# CE842170047_SHEET4.net
KiCad netlist of a schematic drawn in Altium Designer
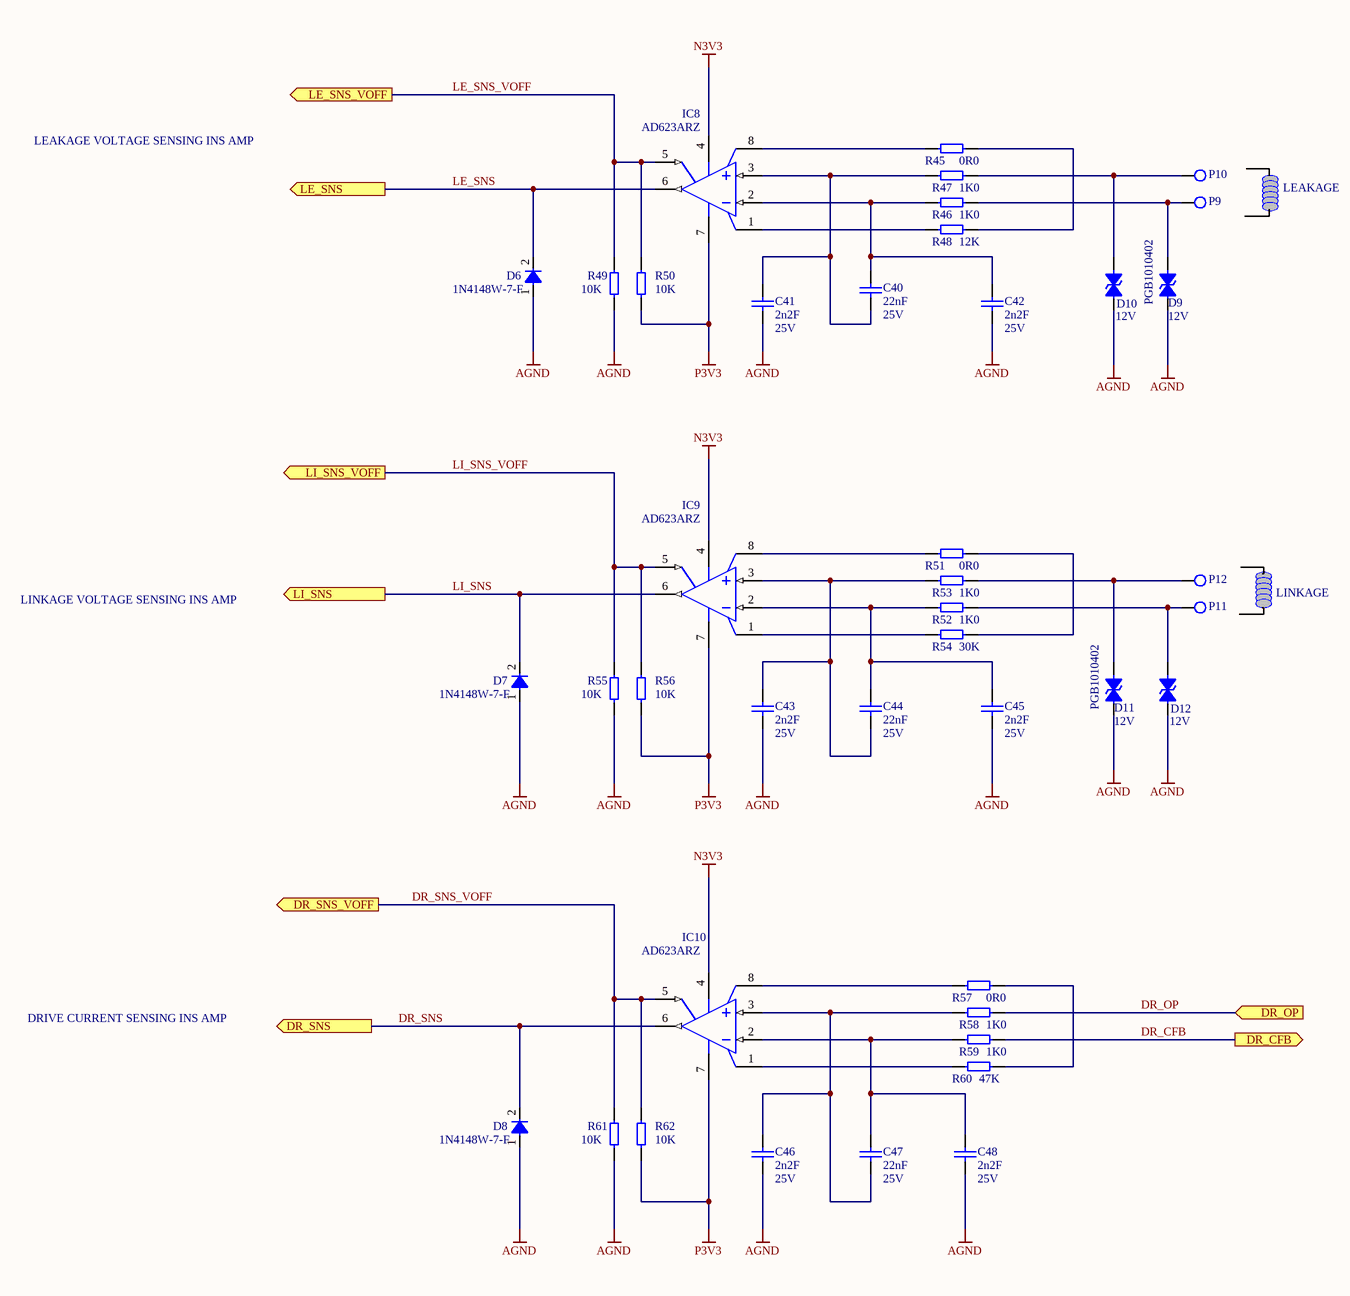
[diagram p0: CE842170047_SHEET4.SchDoc]

(export (version "E")
  (design (tool "Eeschema 10.0.6"))
  (components
    (comp (ref "C40")
      (value "22nF")
      (footprint "C0603")
      (description "CAPACITOR CERAMIC 0603 25V 10% X7R 22nF")
      (fields
        (field (name "VOLTAGE") "25V")
        (field (name "PII_PARTNUMBER") "KK/96159/3434")
        (field (name "TOLERANCE") "10%")
      )
      (libsource (lib "AltiumComponents") (part "CAP_GENERIC"))
    )
    (comp (ref "C41")
      (value "2n2F")
      (footprint "C0603")
      (description "CAPACITOR_2.2nF_10%_25V_603")
      (fields
        (field (name "VOLTAGE") "25V")
        (field (name "PII_PARTNUMBER") "KK/96159/4334")
        (field (name "TOLERANCE") "10%")
      )
      (libsource (lib "AltiumComponents") (part "CAP_GENERIC"))
    )
    (comp (ref "C42")
      (value "2n2F")
      (footprint "C0603")
      (description "CAPACITOR_2.2nF_10%_25V_603")
      (fields
        (field (name "VOLTAGE") "25V")
        (field (name "PII_PARTNUMBER") "KK/96159/4334")
        (field (name "TOLERANCE") "10%")
      )
      (libsource (lib "AltiumComponents") (part "CAP_GENERIC"))
    )
    (comp (ref "C43")
      (value "2n2F")
      (footprint "C0603")
      (description "CAPACITOR_2.2nF_10%_25V_603")
      (fields
        (field (name "VOLTAGE") "25V")
        (field (name "PII_PARTNUMBER") "KK/96159/4334")
        (field (name "TOLERANCE") "10%")
      )
      (libsource (lib "AltiumComponents") (part "CAP_GENERIC"))
    )
    (comp (ref "C44")
      (value "22nF")
      (footprint "C0603")
      (description "CAPACITOR CERAMIC 0603 25V 10% X7R 22nF")
      (fields
        (field (name "VOLTAGE") "25V")
        (field (name "PII_PARTNUMBER") "KK/96159/3434")
        (field (name "TOLERANCE") "10%")
      )
      (libsource (lib "AltiumComponents") (part "CAP_GENERIC"))
    )
    (comp (ref "C45")
      (value "2n2F")
      (footprint "C0603")
      (description "CAPACITOR_2.2nF_10%_25V_603")
      (fields
        (field (name "VOLTAGE") "25V")
        (field (name "PII_PARTNUMBER") "KK/96159/4334")
        (field (name "TOLERANCE") "10%")
      )
      (libsource (lib "AltiumComponents") (part "CAP_GENERIC"))
    )
    (comp (ref "C46")
      (value "2n2F")
      (footprint "C0603")
      (description "CAPACITOR_2.2nF_10%_25V_603")
      (fields
        (field (name "VOLTAGE") "25V")
        (field (name "PII_PARTNUMBER") "KK/96159/4334")
        (field (name "TOLERANCE") "10%")
      )
      (libsource (lib "AltiumComponents") (part "CAP_GENERIC"))
    )
    (comp (ref "C47")
      (value "22nF")
      (footprint "C0603")
      (description "CAPACITOR CERAMIC 0603 25V 10% X7R 22nF")
      (fields
        (field (name "VOLTAGE") "25V")
        (field (name "PII_PARTNUMBER") "KK/96159/3434")
        (field (name "TOLERANCE") "10%")
      )
      (libsource (lib "AltiumComponents") (part "CAP_GENERIC"))
    )
    (comp (ref "C48")
      (value "2n2F")
      (footprint "C0603")
      (description "CAPACITOR_2.2nF_10%_25V_603")
      (fields
        (field (name "VOLTAGE") "25V")
        (field (name "PII_PARTNUMBER") "KK/96159/4334")
        (field (name "TOLERANCE") "10%")
      )
      (libsource (lib "AltiumComponents") (part "CAP_GENERIC"))
    )
    (comp (ref "D6")
      (value "KK/95048/0189")
      (footprint "SOD-123")
      (description "DIODE SWITCHING POWER")
      (fields
        (field (name "MF_PARTNUMBER") "1N4148W-7-F")
        (field (name "POWER") "2A")
        (field (name "VOLTAGE") "100V")
      )
      (libsource (lib "AltiumComponents") (part "DIODE_GENERIC"))
    )
    (comp (ref "D7")
      (value "KK/95048/0189")
      (footprint "SOD-123")
      (description "DIODE SWITCHING POWER")
      (fields
        (field (name "MF_PARTNUMBER") "1N4148W-7-F")
        (field (name "POWER") "2A")
        (field (name "VOLTAGE") "100V")
      )
      (libsource (lib "AltiumComponents") (part "DIODE_GENERIC"))
    )
    (comp (ref "D8")
      (value "KK/95048/0189")
      (footprint "SOD-123")
      (description "DIODE SWITCHING POWER")
      (fields
        (field (name "MF_PARTNUMBER") "1N4148W-7-F")
        (field (name "POWER") "2A")
        (field (name "VOLTAGE") "100V")
      )
      (libsource (lib "AltiumComponents") (part "DIODE_GENERIC"))
    )
    (comp (ref "D9")
      (value "KK/95070/0036")
      (footprint "ESD0402")
      (description "SUPPRESSOR ESD,SMD,0402,12VDC,LIF,PGB1010402")
      (fields
        (field (name "MF_PARTNUMBER") "PGB1010402")
        (field (name "VOLTAGE") "12V")
        (field (name "MANUFACTURER") "LITTELFUSE")
      )
      (libsource (lib "AltiumComponents") (part "TVS_DIODE_BIDIR"))
    )
    (comp (ref "D10")
      (value "KK/95070/0036")
      (footprint "ESD0402")
      (description "SUPPRESSOR ESD,SMD,0402,12VDC,LIF,PGB1010402")
      (fields
        (field (name "MF_PARTNUMBER") "PGB1010402")
        (field (name "VOLTAGE") "12V")
        (field (name "MANUFACTURER") "LITTELFUSE")
      )
      (libsource (lib "AltiumComponents") (part "TVS_DIODE_BIDIR"))
    )
    (comp (ref "D11")
      (value "KK/95070/0036")
      (footprint "ESD0402")
      (description "SUPPRESSOR ESD,SMD,0402,12VDC,LIF,PGB1010402")
      (fields
        (field (name "MF_PARTNUMBER") "PGB1010402")
        (field (name "VOLTAGE") "12V")
        (field (name "MANUFACTURER") "LITTELFUSE")
      )
      (libsource (lib "AltiumComponents") (part "TVS_DIODE_BIDIR"))
    )
    (comp (ref "D12")
      (value "KK/95070/0036")
      (footprint "ESD0402")
      (description "SUPPRESSOR ESD,SMD,0402,12VDC,LIF,PGB1010402")
      (fields
        (field (name "MF_PARTNUMBER") "PGB1010402")
        (field (name "VOLTAGE") "12V")
        (field (name "MANUFACTURER") "LITTELFUSE")
      )
      (libsource (lib "AltiumComponents") (part "TVS_DIODE_BIDIR"))
    )
    (comp (ref "IC8")
      (value "KK/95312/0245")
      (footprint "SOIC-8")
      (description "SINGLE RAIL to RAIL INSTRUMENTATION AMPLIFIER")
      (fields
        (field (name "MANUFACTURER") "Analog Devices")
        (field (name "MANUFACTURER PART NUMBER") "AD623ARZ")
        (field (name "MF_PARTNUMBER") "AD623ARZ")
      )
      (libsource (lib "AltiumComponents") (part "AD623"))
    )
    (comp (ref "IC9")
      (value "KK/95312/0245")
      (footprint "SOIC-8")
      (description "SINGLE RAIL to RAIL INSTRUMENTATION AMPLIFIER")
      (fields
        (field (name "MANUFACTURER") "Analog Devices")
        (field (name "MANUFACTURER PART NUMBER") "AD623ARZ")
        (field (name "MF_PARTNUMBER") "AD623ARZ")
      )
      (libsource (lib "AltiumComponents") (part "AD623"))
    )
    (comp (ref "IC10")
      (value "KK/95312/0245")
      (footprint "SOIC-8")
      (description "SINGLE RAIL to RAIL INSTRUMENTATION AMPLIFIER")
      (fields
        (field (name "MANUFACTURER") "Analog Devices")
        (field (name "MANUFACTURER PART NUMBER") "AD623ARZ")
        (field (name "MF_PARTNUMBER") "AD623ARZ")
      )
      (libsource (lib "AltiumComponents") (part "AD623"))
    )
    (comp (ref "P9")
      (value "TESTPAD1")
      (footprint "P0.8xH0.5")
      (description "P0.8 X H0.5 X 0.9SM")
      (fields (field (name "MANUFACTURER") "PCB MANUFACTURER"))
      (libsource (lib "AltiumComponents") (part "TP_GENERIC"))
    )
    (comp (ref "P10")
      (value "TESTPAD1")
      (footprint "P0.8xH0.5")
      (description "P0.8 X H0.5 X 0.9SM")
      (fields (field (name "MANUFACTURER") "PCB MANUFACTURER"))
      (libsource (lib "AltiumComponents") (part "TP_GENERIC"))
    )
    (comp (ref "P11")
      (value "TESTPAD1")
      (footprint "P0.8xH0.5")
      (description "P0.8 X H0.5 X 0.9SM")
      (fields (field (name "MANUFACTURER") "PCB MANUFACTURER"))
      (libsource (lib "AltiumComponents") (part "TP_GENERIC"))
    )
    (comp (ref "P12")
      (value "TESTPAD1")
      (footprint "P0.8xH0.5")
      (description "P0.8 X H0.5 X 0.9SM")
      (fields (field (name "MANUFACTURER") "PCB MANUFACTURER"))
      (libsource (lib "AltiumComponents") (part "TP_GENERIC"))
    )
    (comp (ref "R45")
      (value "0R0")
      (footprint "R0603")
      (description "ZERO OHM LINK")
      (fields (field (name "PII_PARTNUMBER") "KK/96059/0000") (field (name "POWER") "63mW"))
      (libsource (lib "") (part "RES_GENERIC_1"))
    )
    (comp (ref "R46")
      (value "1K0")
      (footprint "R0603")
      (description "RESISTOR_1K0_1%_0603J_63mW")
      (fields (field (name "PII_PARTNUMBER") "KK/96059/0501") (field (name "TOLERANCE") "1%"))
      (libsource (lib "AltiumComponents") (part "RES_GENERIC"))
    )
    (comp (ref "R47")
      (value "1K0")
      (footprint "R0603")
      (description "RESISTOR_1K0_1%_0603J_63mW")
      (fields (field (name "PII_PARTNUMBER") "KK/96059/0501") (field (name "TOLERANCE") "1%"))
      (libsource (lib "AltiumComponents") (part "RES_GENERIC"))
    )
    (comp (ref "R48")
      (value "12K")
      (footprint "R0603")
      (description "RESISTOR 0603 0.063W 1% 12K")
      (fields (field (name "PII_PARTNUMBER") "KK/96059/0609") (field (name "TOLERANCE") "1%"))
      (libsource (lib "") (part "RES_GENERIC_1"))
    )
    (comp (ref "R49")
      (value "10K")
      (footprint "R0603")
      (description "RESISTOR_10K_1%_0603J_63mW")
      (fields (field (name "PII_PARTNUMBER") "KK/96059/0601") (field (name "TOLERANCE") "1%"))
      (libsource (lib "") (part "RES_GENERIC_2"))
    )
    (comp (ref "R50")
      (value "10K")
      (footprint "R0603")
      (description "RESISTOR_10K_1%_0603J_63mW")
      (fields (field (name "PII_PARTNUMBER") "KK/96059/0601") (field (name "TOLERANCE") "1%"))
      (libsource (lib "") (part "RES_GENERIC_2"))
    )
    (comp (ref "R51")
      (value "0R0")
      (footprint "R0603")
      (description "ZERO OHM LINK")
      (fields (field (name "PII_PARTNUMBER") "KK/96059/0000") (field (name "POWER") "63mW"))
      (libsource (lib "") (part "RES_GENERIC_1"))
    )
    (comp (ref "R52")
      (value "1K0")
      (footprint "R0603")
      (description "RESISTOR_1K0_1%_0603J_63mW")
      (fields (field (name "PII_PARTNUMBER") "KK/96059/0501") (field (name "TOLERANCE") "1%"))
      (libsource (lib "AltiumComponents") (part "RES_GENERIC"))
    )
    (comp (ref "R53")
      (value "1K0")
      (footprint "R0603")
      (description "RESISTOR_1K0_1%_0603J_63mW")
      (fields (field (name "PII_PARTNUMBER") "KK/96059/0501") (field (name "TOLERANCE") "1%"))
      (libsource (lib "AltiumComponents") (part "RES_GENERIC"))
    )
    (comp (ref "R54")
      (value "30K")
      (footprint "R0603")
      (description "RESISTOR_30K_1%_0603_63mW")
      (fields (field (name "PII_PARTNUMBER") "KK/96059/0647") (field (name "TOLERANCE") "1%"))
      (libsource (lib "") (part "RES_GENERIC_1"))
    )
    (comp (ref "R55")
      (value "10K")
      (footprint "R0603")
      (description "RESISTOR_10K_1%_0603J_63mW")
      (fields (field (name "PII_PARTNUMBER") "KK/96059/0601") (field (name "TOLERANCE") "1%"))
      (libsource (lib "") (part "RES_GENERIC_2"))
    )
    (comp (ref "R56")
      (value "10K")
      (footprint "R0603")
      (description "RESISTOR_10K_1%_0603J_63mW")
      (fields (field (name "PII_PARTNUMBER") "KK/96059/0601") (field (name "TOLERANCE") "1%"))
      (libsource (lib "") (part "RES_GENERIC_2"))
    )
    (comp (ref "R57")
      (value "0R0")
      (footprint "R0603")
      (description "ZERO OHM LINK")
      (fields (field (name "PII_PARTNUMBER") "KK/96059/0000") (field (name "POWER") "63mW"))
      (libsource (lib "") (part "RES_GENERIC_1"))
    )
    (comp (ref "R58")
      (value "1K0")
      (footprint "R0603")
      (description "RESISTOR_1K0_1%_0603J_63mW")
      (fields (field (name "PII_PARTNUMBER") "KK/96059/0501") (field (name "TOLERANCE") "1%"))
      (libsource (lib "AltiumComponents") (part "RES_GENERIC"))
    )
    (comp (ref "R59")
      (value "1K0")
      (footprint "R0603")
      (description "RESISTOR_1K0_1%_0603J_63mW")
      (fields (field (name "PII_PARTNUMBER") "KK/96059/0501") (field (name "TOLERANCE") "1%"))
      (libsource (lib "AltiumComponents") (part "RES_GENERIC"))
    )
    (comp (ref "R60")
      (value "47K")
      (footprint "R0603")
      (description "RESISTOR,SMD,0603,0.1W,1%,47K")
      (fields (field (name "PII_PARTNUMBER") "KK/96059/4666") (field (name "TOLERANCE") "1%"))
      (libsource (lib "") (part "RES_GENERIC_1"))
    )
    (comp (ref "R61")
      (value "10K")
      (footprint "R0603")
      (description "RESISTOR_10K_1%_0603J_63mW")
      (fields (field (name "PII_PARTNUMBER") "KK/96059/0601") (field (name "TOLERANCE") "1%"))
      (libsource (lib "") (part "RES_GENERIC_2"))
    )
    (comp (ref "R62")
      (value "10K")
      (footprint "R0603")
      (description "RESISTOR_10K_1%_0603J_63mW")
      (fields (field (name "PII_PARTNUMBER") "KK/96059/0601") (field (name "TOLERANCE") "1%"))
      (libsource (lib "") (part "RES_GENERIC_2"))
    )
  )
  (nets
    (net (code "1") (name "/DR_CFB") (class "Default")
      (node (ref "R59") (pin "1") (pinfunction "1_1") (pintype "passive"))
    )
    (net (code "2") (name "/DR_OP") (class "Default")
      (node (ref "R58") (pin "1") (pinfunction "1_1") (pintype "passive"))
    )
    (net (code "3") (name "/DR_SNS") (class "Default")
      (node (ref "D8") (pin "2") (pinfunction "K_2") (pintype "passive"))
      (node (ref "IC10") (pin "6") (pinfunction "OUTPUT_6") (pintype "output"))
    )
    (net (code "4") (name "/DR_SNS_VOFF") (class "Default")
      (node (ref "IC10") (pin "5") (pinfunction "REF_5") (pintype "input"))
      (node (ref "R61") (pin "2") (pinfunction "2_2") (pintype "passive"))
      (node (ref "R62") (pin "2") (pinfunction "2_2") (pintype "passive"))
    )
    (net (code "5") (name "/LE_SNS") (class "Default")
      (node (ref "D6") (pin "2") (pinfunction "K_2") (pintype "passive"))
      (node (ref "IC8") (pin "6") (pinfunction "OUTPUT_6") (pintype "output"))
    )
    (net (code "6") (name "/LE_SNS_VOFF") (class "Default")
      (node (ref "IC8") (pin "5") (pinfunction "REF_5") (pintype "input"))
      (node (ref "R49") (pin "2") (pinfunction "2_2") (pintype "passive"))
      (node (ref "R50") (pin "2") (pinfunction "2_2") (pintype "passive"))
    )
    (net (code "7") (name "/LI_SNS") (class "Default")
      (node (ref "D7") (pin "2") (pinfunction "K_2") (pintype "passive"))
      (node (ref "IC9") (pin "6") (pinfunction "OUTPUT_6") (pintype "output"))
    )
    (net (code "8") (name "/LI_SNS_VOFF") (class "Default")
      (node (ref "IC9") (pin "5") (pinfunction "REF_5") (pintype "input"))
      (node (ref "R55") (pin "2") (pinfunction "2_2") (pintype "passive"))
      (node (ref "R56") (pin "2") (pinfunction "2_2") (pintype "passive"))
    )
    (net (code "9") (name "AGND") (class "Default")
      (node (ref "C41") (pin "2") (pinfunction "2_2") (pintype "passive"))
      (node (ref "C42") (pin "2") (pinfunction "2_2") (pintype "passive"))
      (node (ref "C43") (pin "2") (pinfunction "2_2") (pintype "passive"))
      (node (ref "C45") (pin "2") (pinfunction "2_2") (pintype "passive"))
      (node (ref "C46") (pin "2") (pinfunction "2_2") (pintype "passive"))
      (node (ref "C48") (pin "2") (pinfunction "2_2") (pintype "passive"))
      (node (ref "D10") (pin "1") (pinfunction "1_1") (pintype "passive"))
      (node (ref "D11") (pin "1") (pinfunction "1_1") (pintype "passive"))
      (node (ref "D12") (pin "1") (pinfunction "1_1") (pintype "passive"))
      (node (ref "D6") (pin "1") (pinfunction "A_1") (pintype "passive"))
      (node (ref "D7") (pin "1") (pinfunction "A_1") (pintype "passive"))
      (node (ref "D8") (pin "1") (pinfunction "A_1") (pintype "passive"))
      (node (ref "D9") (pin "1") (pinfunction "1_1") (pintype "passive"))
      (node (ref "R49") (pin "1") (pinfunction "1_1") (pintype "passive"))
      (node (ref "R55") (pin "1") (pinfunction "1_1") (pintype "passive"))
      (node (ref "R61") (pin "1") (pinfunction "1_1") (pintype "passive"))
    )
    (net (code "10") (name "N3V3") (class "Default")
      (node (ref "IC10") (pin "4") (pinfunction "-VS_4") (pintype "power_in"))
      (node (ref "IC8") (pin "4") (pinfunction "-VS_4") (pintype "power_in"))
      (node (ref "IC9") (pin "4") (pinfunction "-VS_4") (pintype "power_in"))
    )
    (net (code "11") (name "Net-(D9-Pad2)") (class "Default")
      (node (ref "D9") (pin "2") (pinfunction "2_2") (pintype "passive"))
      (node (ref "P9") (pin "1") (pinfunction "1_1") (pintype "passive"))
      (node (ref "R46") (pin "1") (pinfunction "1_1") (pintype "passive"))
    )
    (net (code "12") (name "Net-(D10-Pad2)") (class "Default")
      (node (ref "D10") (pin "2") (pinfunction "2_2") (pintype "passive"))
      (node (ref "P10") (pin "1") (pinfunction "1_1") (pintype "passive"))
      (node (ref "R47") (pin "1") (pinfunction "1_1") (pintype "passive"))
    )
    (net (code "13") (name "Net-(D11-Pad2)") (class "Default")
      (node (ref "D11") (pin "2") (pinfunction "2_2") (pintype "passive"))
      (node (ref "P12") (pin "1") (pinfunction "1_1") (pintype "passive"))
      (node (ref "R53") (pin "1") (pinfunction "1_1") (pintype "passive"))
    )
    (net (code "14") (name "Net-(D12-Pad2)") (class "Default")
      (node (ref "D12") (pin "2") (pinfunction "2_2") (pintype "passive"))
      (node (ref "P11") (pin "1") (pinfunction "1_1") (pintype "passive"))
      (node (ref "R52") (pin "1") (pinfunction "1_1") (pintype "passive"))
    )
    (net (code "15") (name "Net-(IC8-+IN)") (class "Default")
      (node (ref "C40") (pin "2") (pinfunction "2_2") (pintype "passive"))
      (node (ref "C41") (pin "1") (pinfunction "1_1") (pintype "passive"))
      (node (ref "IC8") (pin "3") (pinfunction "+IN_3") (pintype "input"))
      (node (ref "R47") (pin "2") (pinfunction "2_2") (pintype "passive"))
    )
    (net (code "16") (name "Net-(IC8-+RG)") (class "Default")
      (node (ref "IC8") (pin "8") (pinfunction "+RG_8") (pintype "passive"))
      (node (ref "R45") (pin "1") (pinfunction "1_1") (pintype "passive"))
    )
    (net (code "17") (name "Net-(IC8--IN)") (class "Default")
      (node (ref "C40") (pin "1") (pinfunction "1_1") (pintype "passive"))
      (node (ref "C42") (pin "1") (pinfunction "1_1") (pintype "passive"))
      (node (ref "IC8") (pin "2") (pinfunction "-IN_2") (pintype "input"))
      (node (ref "R46") (pin "2") (pinfunction "2_2") (pintype "passive"))
    )
    (net (code "18") (name "Net-(IC8--RG)") (class "Default")
      (node (ref "IC8") (pin "1") (pinfunction "-RG_1") (pintype "passive"))
      (node (ref "R48") (pin "1") (pinfunction "1_1") (pintype "passive"))
    )
    (net (code "19") (name "Net-(IC9-+IN)") (class "Default")
      (node (ref "C43") (pin "1") (pinfunction "1_1") (pintype "passive"))
      (node (ref "C44") (pin "2") (pinfunction "2_2") (pintype "passive"))
      (node (ref "IC9") (pin "3") (pinfunction "+IN_3") (pintype "input"))
      (node (ref "R53") (pin "2") (pinfunction "2_2") (pintype "passive"))
    )
    (net (code "20") (name "Net-(IC9-+RG)") (class "Default")
      (node (ref "IC9") (pin "8") (pinfunction "+RG_8") (pintype "passive"))
      (node (ref "R51") (pin "1") (pinfunction "1_1") (pintype "passive"))
    )
    (net (code "21") (name "Net-(IC9--IN)") (class "Default")
      (node (ref "C44") (pin "1") (pinfunction "1_1") (pintype "passive"))
      (node (ref "C45") (pin "1") (pinfunction "1_1") (pintype "passive"))
      (node (ref "IC9") (pin "2") (pinfunction "-IN_2") (pintype "input"))
      (node (ref "R52") (pin "2") (pinfunction "2_2") (pintype "passive"))
    )
    (net (code "22") (name "Net-(IC9--RG)") (class "Default")
      (node (ref "IC9") (pin "1") (pinfunction "-RG_1") (pintype "passive"))
      (node (ref "R54") (pin "1") (pinfunction "1_1") (pintype "passive"))
    )
    (net (code "23") (name "Net-(IC10-+IN)") (class "Default")
      (node (ref "C46") (pin "1") (pinfunction "1_1") (pintype "passive"))
      (node (ref "C47") (pin "2") (pinfunction "2_2") (pintype "passive"))
      (node (ref "IC10") (pin "3") (pinfunction "+IN_3") (pintype "input"))
      (node (ref "R58") (pin "2") (pinfunction "2_2") (pintype "passive"))
    )
    (net (code "24") (name "Net-(IC10-+RG)") (class "Default")
      (node (ref "IC10") (pin "8") (pinfunction "+RG_8") (pintype "passive"))
      (node (ref "R57") (pin "1") (pinfunction "1_1") (pintype "passive"))
    )
    (net (code "25") (name "Net-(IC10--IN)") (class "Default")
      (node (ref "C47") (pin "1") (pinfunction "1_1") (pintype "passive"))
      (node (ref "C48") (pin "1") (pinfunction "1_1") (pintype "passive"))
      (node (ref "IC10") (pin "2") (pinfunction "-IN_2") (pintype "input"))
      (node (ref "R59") (pin "2") (pinfunction "2_2") (pintype "passive"))
    )
    (net (code "26") (name "Net-(IC10--RG)") (class "Default")
      (node (ref "IC10") (pin "1") (pinfunction "-RG_1") (pintype "passive"))
      (node (ref "R60") (pin "1") (pinfunction "1_1") (pintype "passive"))
    )
    (net (code "27") (name "Net-(R45-Pad2)") (class "Default")
      (node (ref "R45") (pin "2") (pinfunction "2_2") (pintype "passive"))
      (node (ref "R48") (pin "2") (pinfunction "2_2") (pintype "passive"))
    )
    (net (code "28") (name "Net-(R51-Pad2)") (class "Default")
      (node (ref "R51") (pin "2") (pinfunction "2_2") (pintype "passive"))
      (node (ref "R54") (pin "2") (pinfunction "2_2") (pintype "passive"))
    )
    (net (code "29") (name "Net-(R57-Pad2)") (class "Default")
      (node (ref "R57") (pin "2") (pinfunction "2_2") (pintype "passive"))
      (node (ref "R60") (pin "2") (pinfunction "2_2") (pintype "passive"))
    )
    (net (code "30") (name "P3V3") (class "Default")
      (node (ref "IC10") (pin "7") (pinfunction "+VS_7") (pintype "power_in"))
      (node (ref "IC8") (pin "7") (pinfunction "+VS_7") (pintype "power_in"))
      (node (ref "IC9") (pin "7") (pinfunction "+VS_7") (pintype "power_in"))
      (node (ref "R50") (pin "1") (pinfunction "1_1") (pintype "passive"))
      (node (ref "R56") (pin "1") (pinfunction "1_1") (pintype "passive"))
      (node (ref "R62") (pin "1") (pinfunction "1_1") (pintype "passive"))
    )
  )
)
